# design.net
KiCad netlist of a schematic drawn in Altium Designer
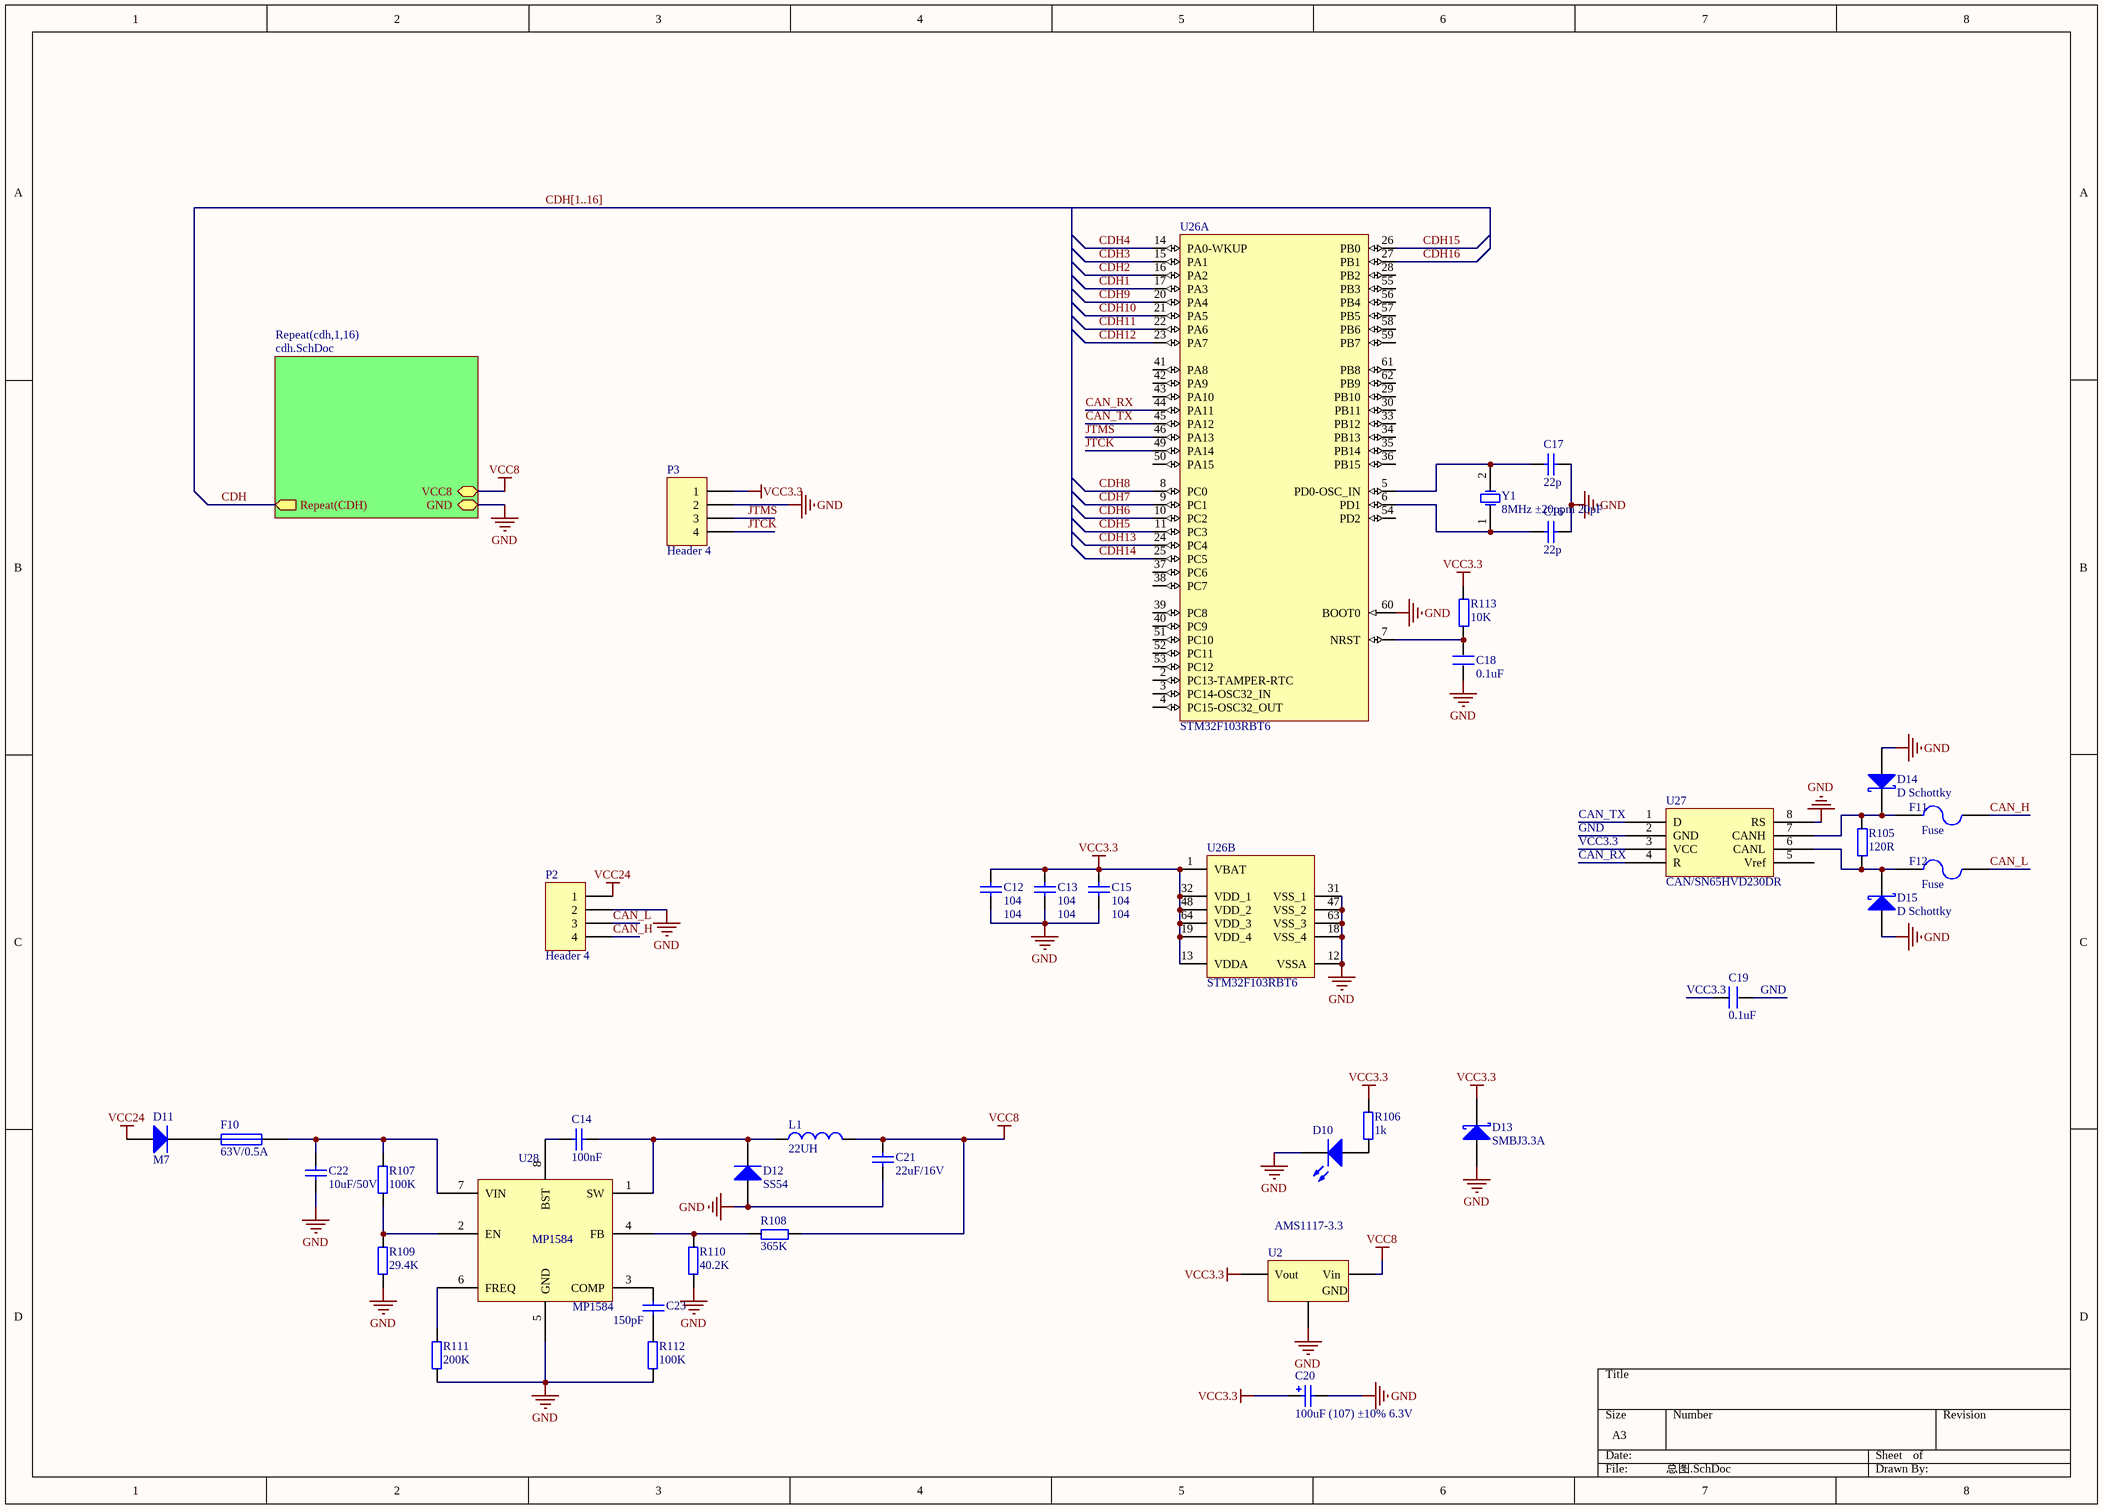
[diagram p0: 总图.SchDoc]

(export (version "E")
  (design (tool "Eeschema 10.0.6"))
  (components
    (comp (ref "C12")
      (value "104")
      (footprint "0603-CAP")
      (description "Capacitor")
      (fields (field (name "ALTIUM_VALUE") "104") (field (name "PUBLISHER") "Altium Limited"))
      (libsource (lib "Miscellaneous Devices") (part "Cap"))
    )
    (comp (ref "C13")
      (value "104")
      (footprint "0603-CAP")
      (description "Capacitor")
      (fields (field (name "ALTIUM_VALUE") "104") (field (name "PUBLISHER") "Altium Limited"))
      (libsource (lib "Miscellaneous Devices") (part "Cap"))
    )
    (comp (ref "C14")
      (value "100nF")
      (footprint "0603-CAP")
      (description "Capacitor (Semiconductor SIM Model)")
      (fields (field (name "Comment") "0.1uF") (field (name "PUBLISHER") "Altium Limited"))
      (libsource (lib "Miscellaneous Devices") (part "Cap Semi"))
    )
    (comp (ref "C15")
      (value "104")
      (footprint "0603-CAP")
      (description "Capacitor")
      (fields (field (name "ALTIUM_VALUE") "104") (field (name "PUBLISHER") "Altium Limited"))
      (libsource (lib "Miscellaneous Devices") (part "Cap"))
    )
    (comp (ref "C16")
      (value "22p")
      (footprint "0603-CAP")
      (description "Capacitor")
      (fields (field (name "PUBLISHER") "Altium Limited"))
      (libsource (lib "Miscellaneous Devices") (part "Cap"))
    )
    (comp (ref "C17")
      (value "22p")
      (footprint "0603-CAP")
      (description "Capacitor")
      (fields (field (name "PUBLISHER") "Altium Limited"))
      (libsource (lib "Miscellaneous Devices") (part "Cap"))
    )
    (comp (ref "C18")
      (value "0.1uF")
      (footprint "0603-CAP")
      (libsource (lib "Explorer STM32F407封装库") (part "C"))
    )
    (comp (ref "C19")
      (value "0.1uF")
      (footprint "0603-CAP")
      (libsource (lib "Explorer STM32F407封装库") (part "C_3"))
    )
    (comp (ref "C20")
      (value "100uF (107) ±10% 6.3V")
      (footprint "CASE-B_3528")
      (description "钽电容")
      (libsource (lib "Miscellaneous Devices LC") (part "3528 100uF (107) 10% 6.3V"))
    )
    (comp (ref "C21")
      (value "22uF/16V")
      (footprint "1206")
      (description "Capacitor (Semiconductor SIM Model)")
      (fields (field (name "Comment") "0.1uF") (field (name "PUBLISHER") "Altium Limited"))
      (libsource (lib "Miscellaneous Devices") (part "Cap Semi"))
    )
    (comp (ref "C22")
      (value "10uF/50V")
      (footprint "1206")
      (description "Capacitor (Semiconductor SIM Model)")
      (fields (field (name "Comment") "0.1uF") (field (name "PUBLISHER") "Altium Limited"))
      (libsource (lib "Miscellaneous Devices") (part "Cap Semi"))
    )
    (comp (ref "C23")
      (value "150pF")
      (footprint "0603-CAP")
      (description "Capacitor (Semiconductor SIM Model)")
      (fields (field (name "Comment") "0.1uF") (field (name "PUBLISHER") "Altium Limited"))
      (libsource (lib "Miscellaneous Devices") (part "Cap Semi"))
    )
    (comp (ref "D10")
      (value "LED0")
      (footprint "LC-0805_LED_S1")
      (description "Typical INFRARED GaAs LED")
      (fields (field (name "PUBLISHER") "Altium Limited"))
      (libsource (lib "继电器板_1") (part "LED0"))
    )
    (comp (ref "D11")
      (value "M7")
      (footprint "SMA(DO-214AC)_S1")
      (description "二极管")
      (libsource (lib "Miscellaneous Devices LC") (part "SMA(DO-214AC) M7"))
    )
    (comp (ref "D12")
      (value "SS54")
      (footprint "SMA(DO-214AC)_S1")
      (description "二极管")
      (libsource (lib "Miscellaneous Devices LC") (part "SMA(DO-214AC) SS54"))
    )
    (comp (ref "D13")
      (value "SMBJ3.3A")
      (footprint "SMB")
      (description "Schottky Diode")
      (fields (field (name "PUBLISHER") "Altium Limited"))
      (libsource (lib "Miscellaneous Devices") (part "D Schottky"))
    )
    (comp (ref "D14")
      (value "D Schottky")
      (footprint "SMB")
      (description "Schottky Diode")
      (fields (field (name "PUBLISHER") "Altium Limited"))
      (libsource (lib "Miscellaneous Devices") (part "D Schottky"))
    )
    (comp (ref "D15")
      (value "D Schottky")
      (footprint "SMB")
      (description "Schottky Diode")
      (fields (field (name "PUBLISHER") "Altium Limited"))
      (libsource (lib "Miscellaneous Devices") (part "D Schottky"))
    )
    (comp (ref "F10")
      (value "63V/0.5A")
      (footprint "1206")
      (description "Fuse")
      (fields (field (name "PUBLISHER") "Altium Limited"))
      (libsource (lib "Miscellaneous Devices") (part "Fuse 1"))
    )
    (comp (ref "F11")
      (value "Fuse")
      (footprint "12Z-2010")
      (fields (field (name "PUBLISHER") "Altium Limited"))
      (libsource (lib "Miscellaneous Devices") (part "Fuse 2"))
    )
    (comp (ref "F12")
      (value "Fuse")
      (footprint "12Z-2010")
      (fields (field (name "PUBLISHER") "Altium Limited"))
      (libsource (lib "Miscellaneous Devices") (part "Fuse 2"))
    )
    (comp (ref "L1")
      (value "22UH")
      (footprint "L-7*7*4mm-S")
      (description "Inductor")
      (fields (field (name "PUBLISHER") "Altium Limited"))
      (libsource (lib "Miscellaneous Devices") (part "Inductor"))
    )
    (comp (ref "P2")
      (value "Header 4")
      (footprint "DZ-4-3.5")
      (description "Header, 4-Pin")
      (fields (field (name "PUBLISHER") "Altium Limited"))
      (libsource (lib "Miscellaneous Connectors") (part "Header 4"))
    )
    (comp (ref "P3")
      (value "Header 4")
      (footprint "HDR1X4")
      (description "Header, 4-Pin")
      (fields (field (name "PUBLISHER") "Altium Limited"))
      (libsource (lib "Miscellaneous Connectors") (part "Header 4"))
    )
    (comp (ref "R105")
      (value "120R")
      (footprint "0603")
      (libsource (lib "Explorer STM32F407封装库") (part "R_2"))
    )
    (comp (ref "R106") (value "1k") (footprint "0603") (libsource (lib "Explorer STM32F407封装库") (part "R_2")))
    (comp (ref "R107")
      (value "100K")
      (footprint "0603")
      (libsource (lib "Explorer STM32F407封装库") (part "R_2"))
    )
    (comp (ref "R108")
      (value "365K")
      (footprint "0603")
      (libsource (lib "Explorer STM32F407封装库") (part "R_2"))
    )
    (comp (ref "R109")
      (value "29.4K")
      (footprint "0603")
      (libsource (lib "Explorer STM32F407封装库") (part "R_2"))
    )
    (comp (ref "R110")
      (value "40.2K")
      (footprint "0603")
      (libsource (lib "Explorer STM32F407封装库") (part "R_2"))
    )
    (comp (ref "R111")
      (value "200K")
      (footprint "0603")
      (libsource (lib "Explorer STM32F407封装库") (part "R_2"))
    )
    (comp (ref "R112")
      (value "100K")
      (footprint "0603")
      (libsource (lib "Explorer STM32F407封装库") (part "R_2"))
    )
    (comp (ref "R113")
      (value "10K")
      (footprint "0603")
      (libsource (lib "Explorer STM32F407封装库") (part "R_2"))
    )
    (comp (ref "U2")
      (value "AMS1117-3.3")
      (footprint "SOT-223")
      (description "低压差线性稳压(LDO)")
      (libsource (lib "Miscellaneous Devices LC") (part "SOT-223 AMS1117-3.3"))
    )
    (comp (ref "U26")
      (value "STM32F103RBT6")
      (footprint "LQFP-64_10x10x05P")
      (description "ARM")
      (libsource (lib "Miscellaneous Devices LC") (part "STM32F103RBT6"))
    )
    (comp (ref "U27")
      (value "CAN/SN65HVD230DR")
      (footprint "SOIC-8_150mil")
      (description "CAN")
      (libsource (lib "Miscellaneous Devices LC") (part "CAN/SN65HVD230DR_[C12084]"))
    )
    (comp (ref "U28") (value "MP1584") (footprint "SO-8") (libsource (lib "磁导航") (part "MP1584EN")))
    (comp (ref "Y1")
      (value "8MHz ±20ppm 20pF")
      (footprint "SMD-5032_2P")
      (description "贴片晶振")
      (libsource (lib "Miscellaneous Devices LC") (part "SMD-5032_2P 8MHz 20ppm 20pF"))
    )
  )
  (nets
    (net (code "1") (name "/CAN_H") (class "Default")
      (node (ref "F11") (pin "1") (pinfunction "1_1") (pintype "passive"))
      (node (ref "P2") (pin "4") (pinfunction "4_4") (pintype "passive"))
    )
    (net (code "2") (name "/CAN_L") (class "Default")
      (node (ref "F12") (pin "1") (pinfunction "1_1") (pintype "passive"))
      (node (ref "P2") (pin "3") (pinfunction "3_3") (pintype "passive"))
    )
    (net (code "3") (name "/CAN_RX") (class "Default")
      (node (ref "U26") (pin "44") (pinfunction "PA11_44") (pintype "bidirectional"))
      (node (ref "U27") (pin "4") (pinfunction "R_4") (pintype "passive"))
    )
    (net (code "4") (name "/CAN_TX") (class "Default")
      (node (ref "U26") (pin "45") (pinfunction "PA12_45") (pintype "bidirectional"))
      (node (ref "U27") (pin "1") (pinfunction "D_1") (pintype "passive"))
    )
    (net (code "6") (name "/CDH1") (class "Default")
      (node (ref "U26") (pin "17") (pinfunction "PA3_17") (pintype "bidirectional"))
    )
    (net (code "7") (name "/CDH2") (class "Default")
      (node (ref "U26") (pin "16") (pinfunction "PA2_16") (pintype "bidirectional"))
    )
    (net (code "8") (name "/CDH3") (class "Default")
      (node (ref "U26") (pin "15") (pinfunction "PA1_15") (pintype "bidirectional"))
    )
    (net (code "9") (name "/CDH4") (class "Default")
      (node (ref "U26") (pin "14") (pinfunction "PA0-WKUP_14") (pintype "bidirectional"))
    )
    (net (code "10") (name "/CDH5") (class "Default")
      (node (ref "U26") (pin "11") (pinfunction "PC3_11") (pintype "bidirectional"))
    )
    (net (code "11") (name "/CDH6") (class "Default")
      (node (ref "U26") (pin "10") (pinfunction "PC2_10") (pintype "bidirectional"))
    )
    (net (code "12") (name "/CDH7") (class "Default")
      (node (ref "U26") (pin "9") (pinfunction "PC1_9") (pintype "bidirectional"))
    )
    (net (code "13") (name "/CDH8") (class "Default")
      (node (ref "U26") (pin "8") (pinfunction "PC0_8") (pintype "bidirectional"))
    )
    (net (code "14") (name "/CDH9") (class "Default")
      (node (ref "U26") (pin "20") (pinfunction "PA4_20") (pintype "bidirectional"))
    )
    (net (code "15") (name "/CDH10") (class "Default")
      (node (ref "U26") (pin "21") (pinfunction "PA5_21") (pintype "bidirectional"))
    )
    (net (code "16") (name "/CDH11") (class "Default")
      (node (ref "U26") (pin "22") (pinfunction "PA6_22") (pintype "bidirectional"))
    )
    (net (code "17") (name "/CDH12") (class "Default")
      (node (ref "U26") (pin "23") (pinfunction "PA7_23") (pintype "bidirectional"))
    )
    (net (code "18") (name "/CDH13") (class "Default")
      (node (ref "U26") (pin "24") (pinfunction "PC4_24") (pintype "bidirectional"))
    )
    (net (code "19") (name "/CDH14") (class "Default")
      (node (ref "U26") (pin "25") (pinfunction "PC5_25") (pintype "bidirectional"))
    )
    (net (code "20") (name "/CDH15") (class "Default")
      (node (ref "U26") (pin "26") (pinfunction "PB0_26") (pintype "bidirectional"))
    )
    (net (code "21") (name "/CDH16") (class "Default")
      (node (ref "U26") (pin "27") (pinfunction "PB1_27") (pintype "bidirectional"))
    )
    (net (code "23") (name "/JTCK") (class "Default")
      (node (ref "P3") (pin "4") (pinfunction "4_4") (pintype "passive"))
      (node (ref "U26") (pin "49") (pinfunction "PA14_49") (pintype "bidirectional"))
    )
    (net (code "24") (name "/JTMS") (class "Default")
      (node (ref "P3") (pin "3") (pinfunction "3_3") (pintype "passive"))
      (node (ref "U26") (pin "46") (pinfunction "PA13_46") (pintype "bidirectional"))
    )
    (net (code "25") (name "GND") (class "Default")
      (node (ref "C12") (pin "2") (pinfunction "2_2") (pintype "passive"))
      (node (ref "C13") (pin "2") (pinfunction "2_2") (pintype "passive"))
      (node (ref "C15") (pin "2") (pinfunction "2_2") (pintype "passive"))
      (node (ref "C16") (pin "2") (pinfunction "2_2") (pintype "passive"))
      (node (ref "C17") (pin "2") (pinfunction "2_2") (pintype "passive"))
      (node (ref "C18") (pin "1") (pintype "passive"))
      (node (ref "C19") (pin "2") (pintype "passive"))
      (node (ref "C20") (pin "2") (pinfunction "2_2") (pintype "passive"))
      (node (ref "C21") (pin "1") (pinfunction "1_1") (pintype "passive"))
      (node (ref "C22") (pin "2") (pinfunction "2_2") (pintype "passive"))
      (node (ref "D10") (pin "K") (pinfunction "K_K") (pintype "passive"))
      (node (ref "D12") (pin "1") (pinfunction "A_1") (pintype "passive"))
      (node (ref "D13") (pin "1") (pinfunction "A_1") (pintype "passive"))
      (node (ref "D14") (pin "1") (pinfunction "A_1") (pintype "passive"))
      (node (ref "D15") (pin "1") (pinfunction "A_1") (pintype "passive"))
      (node (ref "P2") (pin "2") (pinfunction "2_2") (pintype "passive"))
      (node (ref "P3") (pin "2") (pinfunction "2_2") (pintype "passive"))
      (node (ref "R109") (pin "2") (pintype "passive"))
      (node (ref "R110") (pin "2") (pintype "passive"))
      (node (ref "R111") (pin "2") (pintype "passive"))
      (node (ref "R112") (pin "2") (pintype "passive"))
      (node (ref "U2") (pin "1") (pinfunction "GND_1") (pintype "passive"))
      (node (ref "U26") (pin "12") (pinfunction "VSSA_12") (pintype "power_in"))
      (node (ref "U26") (pin "18") (pinfunction "VSS_4_18") (pintype "power_in"))
      (node (ref "U26") (pin "31") (pinfunction "VSS_1_31") (pintype "power_in"))
      (node (ref "U26") (pin "47") (pinfunction "VSS_2_47") (pintype "power_in"))
      (node (ref "U26") (pin "60") (pinfunction "BOOT0_60") (pintype "input"))
      (node (ref "U26") (pin "63") (pinfunction "VSS_3_63") (pintype "power_in"))
      (node (ref "U27") (pin "2") (pinfunction "GND_2") (pintype "passive"))
      (node (ref "U27") (pin "8") (pinfunction "RS_8") (pintype "passive"))
      (node (ref "U28") (pin "5") (pinfunction "GND_5") (pintype "passive"))
    )
    (net (code "26") (name "Net-(C23-Pad1)") (class "Default")
      (node (ref "C23") (pin "1") (pinfunction "1_1") (pintype "passive"))
      (node (ref "R112") (pin "1") (pintype "passive"))
    )
    (net (code "27") (name "Net-(D10-PadA)") (class "Default")
      (node (ref "D10") (pin "A") (pinfunction "A_A") (pintype "passive"))
      (node (ref "R106") (pin "2") (pintype "passive"))
    )
    (net (code "28") (name "Net-(D11-K)") (class "Default")
      (node (ref "D11") (pin "2") (pinfunction "K_2") (pintype "passive"))
      (node (ref "F10") (pin "1") (pinfunction "1_1") (pintype "passive"))
    )
    (net (code "29") (name "Net-(D12-K)") (class "Default")
      (node (ref "C14") (pin "1") (pinfunction "1_1") (pintype "passive"))
      (node (ref "D12") (pin "2") (pinfunction "K_2") (pintype "passive"))
      (node (ref "L1") (pin "1") (pinfunction "1_1") (pintype "passive"))
      (node (ref "U28") (pin "1") (pinfunction "SW_1") (pintype "passive"))
    )
    (net (code "30") (name "Net-(D14-K)") (class "Default")
      (node (ref "D14") (pin "2") (pinfunction "K_2") (pintype "passive"))
      (node (ref "F11") (pin "2") (pinfunction "2_2") (pintype "passive"))
      (node (ref "R105") (pin "2") (pintype "passive"))
      (node (ref "U27") (pin "7") (pinfunction "CANH_7") (pintype "passive"))
    )
    (net (code "31") (name "Net-(D15-K)") (class "Default")
      (node (ref "D15") (pin "2") (pinfunction "K_2") (pintype "passive"))
      (node (ref "F12") (pin "2") (pinfunction "2_2") (pintype "passive"))
      (node (ref "R105") (pin "1") (pintype "passive"))
      (node (ref "U27") (pin "6") (pinfunction "CANL_6") (pintype "passive"))
    )
    (net (code "32") (name "Net-(U26A-NRST)") (class "Default")
      (node (ref "C18") (pin "2") (pintype "passive"))
      (node (ref "R113") (pin "1") (pintype "passive"))
      (node (ref "U26") (pin "7") (pinfunction "NRST_7") (pintype "bidirectional"))
    )
    (net (code "33") (name "Net-(U26A-PD0-OSC_IN)") (class "Default")
      (node (ref "C17") (pin "1") (pinfunction "1_1") (pintype "passive"))
      (node (ref "U26") (pin "5") (pinfunction "PD0-OSC_IN_5") (pintype "bidirectional"))
      (node (ref "Y1") (pin "2") (pinfunction "OSC2_2") (pintype "passive"))
    )
    (net (code "34") (name "Net-(U26A-PD1)") (class "Default")
      (node (ref "C16") (pin "1") (pinfunction "1_1") (pintype "passive"))
      (node (ref "U26") (pin "6") (pinfunction "PD1_6") (pintype "bidirectional"))
      (node (ref "Y1") (pin "1") (pinfunction "OSC1_1") (pintype "passive"))
    )
    (net (code "35") (name "Net-(U28-BST)") (class "Default")
      (node (ref "C14") (pin "2") (pinfunction "2_2") (pintype "passive"))
      (node (ref "U28") (pin "8") (pinfunction "BST_8") (pintype "passive"))
    )
    (net (code "36") (name "Net-(U28-COMP)") (class "Default")
      (node (ref "C23") (pin "2") (pinfunction "2_2") (pintype "passive"))
      (node (ref "U28") (pin "3") (pinfunction "COMP_3") (pintype "passive"))
    )
    (net (code "37") (name "Net-(U28-EN)") (class "Default")
      (node (ref "R107") (pin "2") (pintype "passive"))
      (node (ref "R109") (pin "1") (pintype "passive"))
      (node (ref "U28") (pin "2") (pinfunction "EN_2") (pintype "passive"))
    )
    (net (code "38") (name "Net-(U28-FB)") (class "Default")
      (node (ref "R108") (pin "1") (pintype "passive"))
      (node (ref "R110") (pin "1") (pintype "passive"))
      (node (ref "U28") (pin "4") (pinfunction "FB_4") (pintype "passive"))
    )
    (net (code "39") (name "Net-(U28-FREQ)") (class "Default")
      (node (ref "R111") (pin "1") (pintype "passive"))
      (node (ref "U28") (pin "6") (pinfunction "FREQ_6") (pintype "passive"))
    )
    (net (code "40") (name "Net-(U28-VIN)") (class "Default")
      (node (ref "C22") (pin "1") (pinfunction "1_1") (pintype "passive"))
      (node (ref "F10") (pin "2") (pinfunction "2_2") (pintype "passive"))
      (node (ref "R107") (pin "1") (pintype "passive"))
      (node (ref "U28") (pin "7") (pinfunction "VIN_7") (pintype "passive"))
    )
    (net (code "41") (name "VCC3.3") (class "Default")
      (node (ref "C12") (pin "1") (pinfunction "1_1") (pintype "passive"))
      (node (ref "C13") (pin "1") (pinfunction "1_1") (pintype "passive"))
      (node (ref "C15") (pin "1") (pinfunction "1_1") (pintype "passive"))
      (node (ref "C19") (pin "1") (pintype "passive"))
      (node (ref "C20") (pin "1") (pinfunction "1_1") (pintype "passive"))
      (node (ref "D13") (pin "2") (pinfunction "K_2") (pintype "passive"))
      (node (ref "P3") (pin "1") (pinfunction "1_1") (pintype "passive"))
      (node (ref "R106") (pin "1") (pintype "passive"))
      (node (ref "R113") (pin "2") (pintype "passive"))
      (node (ref "U2") (pin "2") (pinfunction "Vout_2") (pintype "passive"))
      (node (ref "U26") (pin "1") (pinfunction "VBAT_1") (pintype "power_in"))
      (node (ref "U26") (pin "13") (pinfunction "VDDA_13") (pintype "power_in"))
      (node (ref "U26") (pin "19") (pinfunction "VDD_4_19") (pintype "power_in"))
      (node (ref "U26") (pin "32") (pinfunction "VDD_1_32") (pintype "power_in"))
      (node (ref "U26") (pin "48") (pinfunction "VDD_2_48") (pintype "power_in"))
      (node (ref "U26") (pin "64") (pinfunction "VDD_3_64") (pintype "power_in"))
      (node (ref "U27") (pin "3") (pinfunction "VCC_3") (pintype "passive"))
    )
    (net (code "42") (name "VCC8") (class "Default")
      (node (ref "C21") (pin "2") (pinfunction "2_2") (pintype "passive"))
      (node (ref "L1") (pin "2") (pinfunction "2_2") (pintype "passive"))
      (node (ref "R108") (pin "2") (pintype "passive"))
      (node (ref "U2") (pin "3") (pinfunction "Vin_3") (pintype "passive"))
    )
    (net (code "43") (name "VCC24") (class "Default")
      (node (ref "D11") (pin "1") (pinfunction "A_1") (pintype "passive"))
      (node (ref "P2") (pin "1") (pinfunction "1_1") (pintype "passive"))
    )
    (net (code "44") (name "unconnected-(U26A-PA8-Pad41)") (class "Default")
      (node (ref "U26") (pin "41") (pinfunction "PA8_41") (pintype "bidirectional"))
    )
    (net (code "45") (name "unconnected-(U26A-PA9-Pad42)") (class "Default")
      (node (ref "U26") (pin "42") (pinfunction "PA9_42") (pintype "bidirectional"))
    )
    (net (code "46") (name "unconnected-(U26A-PA10-Pad43)") (class "Default")
      (node (ref "U26") (pin "43") (pinfunction "PA10_43") (pintype "bidirectional"))
    )
    (net (code "47") (name "unconnected-(U26A-PA15-Pad50)") (class "Default")
      (node (ref "U26") (pin "50") (pinfunction "PA15_50") (pintype "bidirectional"))
    )
    (net (code "48") (name "unconnected-(U26A-PB2-Pad28)") (class "Default")
      (node (ref "U26") (pin "28") (pinfunction "PB2_28") (pintype "bidirectional"))
    )
    (net (code "49") (name "unconnected-(U26A-PB3-Pad55)") (class "Default")
      (node (ref "U26") (pin "55") (pinfunction "PB3_55") (pintype "bidirectional"))
    )
    (net (code "50") (name "unconnected-(U26A-PB4-Pad56)") (class "Default")
      (node (ref "U26") (pin "56") (pinfunction "PB4_56") (pintype "bidirectional"))
    )
    (net (code "51") (name "unconnected-(U26A-PB5-Pad57)") (class "Default")
      (node (ref "U26") (pin "57") (pinfunction "PB5_57") (pintype "bidirectional"))
    )
    (net (code "52") (name "unconnected-(U26A-PB6-Pad58)") (class "Default")
      (node (ref "U26") (pin "58") (pinfunction "PB6_58") (pintype "bidirectional"))
    )
    (net (code "53") (name "unconnected-(U26A-PB7-Pad59)") (class "Default")
      (node (ref "U26") (pin "59") (pinfunction "PB7_59") (pintype "bidirectional"))
    )
    (net (code "54") (name "unconnected-(U26A-PB8-Pad61)") (class "Default")
      (node (ref "U26") (pin "61") (pinfunction "PB8_61") (pintype "bidirectional"))
    )
    (net (code "55") (name "unconnected-(U26A-PB9-Pad62)") (class "Default")
      (node (ref "U26") (pin "62") (pinfunction "PB9_62") (pintype "bidirectional"))
    )
    (net (code "56") (name "unconnected-(U26A-PB10-Pad29)") (class "Default")
      (node (ref "U26") (pin "29") (pinfunction "PB10_29") (pintype "bidirectional"))
    )
    (net (code "57") (name "unconnected-(U26A-PB11-Pad30)") (class "Default")
      (node (ref "U26") (pin "30") (pinfunction "PB11_30") (pintype "bidirectional"))
    )
    (net (code "58") (name "unconnected-(U26A-PB12-Pad33)") (class "Default")
      (node (ref "U26") (pin "33") (pinfunction "PB12_33") (pintype "bidirectional"))
    )
    (net (code "59") (name "unconnected-(U26A-PB13-Pad34)") (class "Default")
      (node (ref "U26") (pin "34") (pinfunction "PB13_34") (pintype "bidirectional"))
    )
    (net (code "60") (name "unconnected-(U26A-PB14-Pad35)") (class "Default")
      (node (ref "U26") (pin "35") (pinfunction "PB14_35") (pintype "bidirectional"))
    )
    (net (code "61") (name "unconnected-(U26A-PB15-Pad36)") (class "Default")
      (node (ref "U26") (pin "36") (pinfunction "PB15_36") (pintype "bidirectional"))
    )
    (net (code "62") (name "unconnected-(U26A-PC6-Pad37)") (class "Default")
      (node (ref "U26") (pin "37") (pinfunction "PC6_37") (pintype "bidirectional"))
    )
    (net (code "63") (name "unconnected-(U26A-PC7-Pad38)") (class "Default")
      (node (ref "U26") (pin "38") (pinfunction "PC7_38") (pintype "bidirectional"))
    )
    (net (code "64") (name "unconnected-(U26A-PC8-Pad39)") (class "Default")
      (node (ref "U26") (pin "39") (pinfunction "PC8_39") (pintype "bidirectional"))
    )
    (net (code "65") (name "unconnected-(U26A-PC9-Pad40)") (class "Default")
      (node (ref "U26") (pin "40") (pinfunction "PC9_40") (pintype "bidirectional"))
    )
    (net (code "66") (name "unconnected-(U26A-PC10-Pad51)") (class "Default")
      (node (ref "U26") (pin "51") (pinfunction "PC10_51") (pintype "bidirectional"))
    )
    (net (code "67") (name "unconnected-(U26A-PC11-Pad52)") (class "Default")
      (node (ref "U26") (pin "52") (pinfunction "PC11_52") (pintype "bidirectional"))
    )
    (net (code "68") (name "unconnected-(U26A-PC12-Pad53)") (class "Default")
      (node (ref "U26") (pin "53") (pinfunction "PC12_53") (pintype "bidirectional"))
    )
    (net (code "69") (name "unconnected-(U26A-PC13-TAMPER-RTC-Pad2)") (class "Default")
      (node (ref "U26") (pin "2") (pinfunction "PC13-TAMPER-RTC_2") (pintype "bidirectional"))
    )
    (net (code "70") (name "unconnected-(U26A-PC14-OSC32_IN-Pad3)") (class "Default")
      (node (ref "U26") (pin "3") (pinfunction "PC14-OSC32_IN_3") (pintype "bidirectional"))
    )
    (net (code "71") (name "unconnected-(U26A-PC15-OSC32_OUT-Pad4)") (class "Default")
      (node (ref "U26") (pin "4") (pinfunction "PC15-OSC32_OUT_4") (pintype "bidirectional"))
    )
    (net (code "72") (name "unconnected-(U26A-PD2-Pad54)") (class "Default")
      (node (ref "U26") (pin "54") (pinfunction "PD2_54") (pintype "bidirectional"))
    )
    (net (code "73") (name "unconnected-(U27-Vref-Pad5)") (class "Default")
      (node (ref "U27") (pin "5") (pinfunction "Vref_5") (pintype "passive"))
    )
  )
)
